# USB.net
KiCad netlist of a schematic drawn in Altium Designer
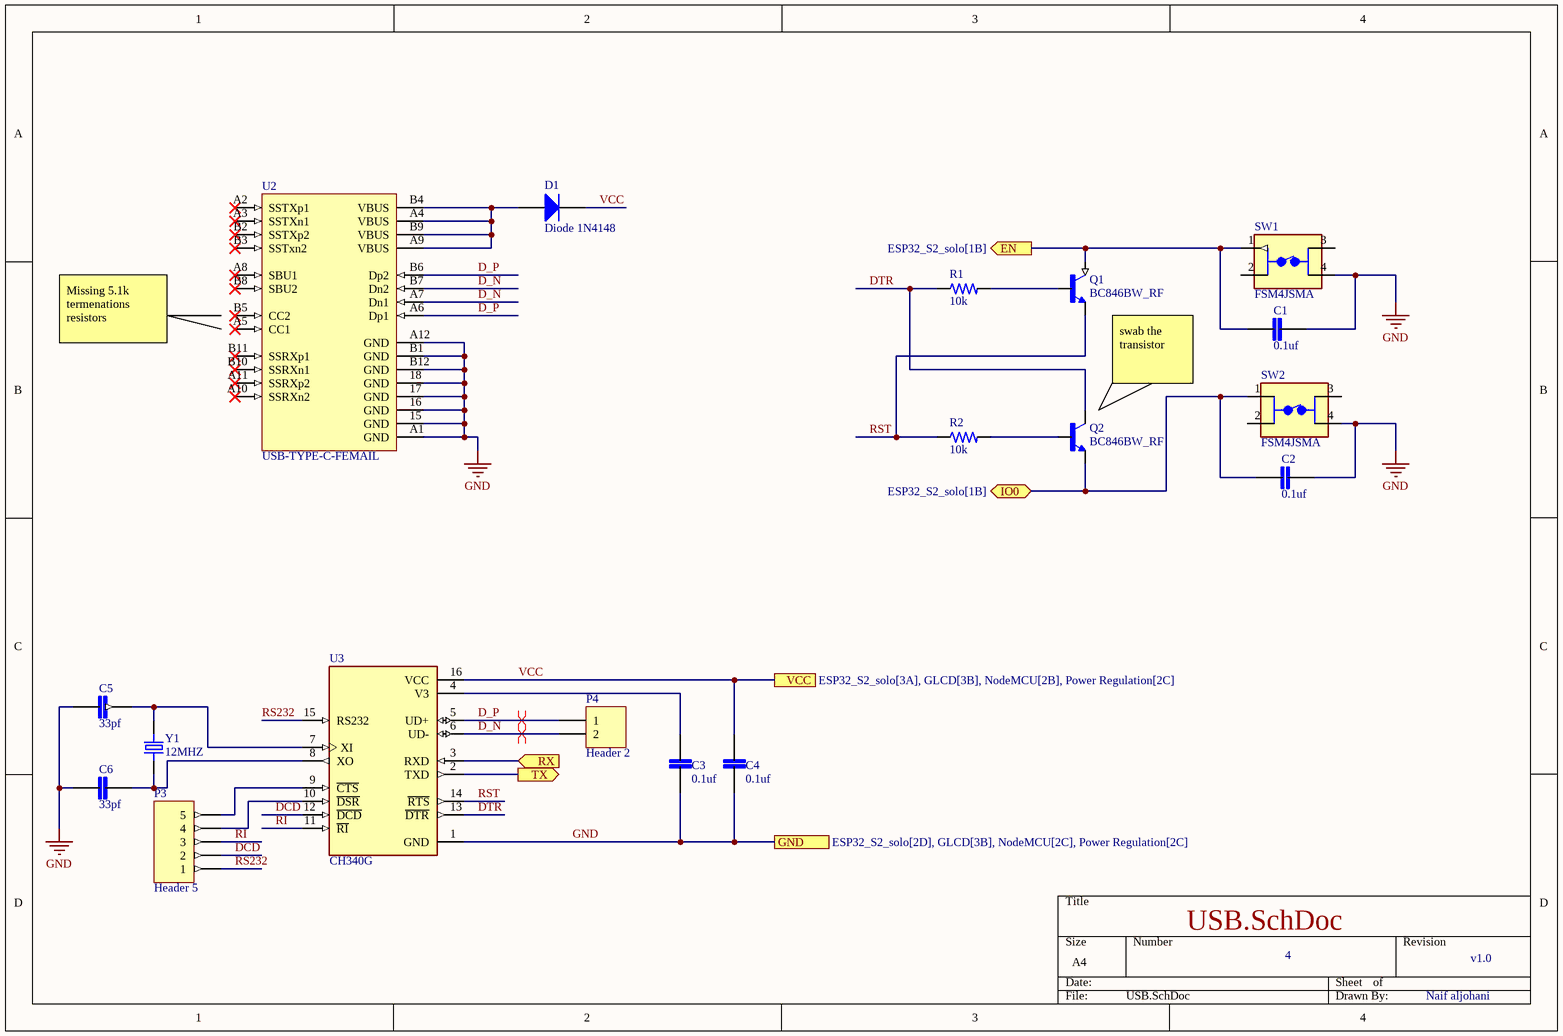
[diagram p0: USB.SchDoc]

(export (version "E")
  (design (tool "Eeschema 10.0.6"))
  (components
    (comp (ref "C1")
      (value "0.1uf")
      (footprint "CAPC2012X140N")
      (description "120PF 100V 10% 0805")
      (fields (field (name "MF") "{'manufacturer': u'AVX'}") (field (name "MP") "LD051A121KAB2A"))
      (libsource (lib "") (part "LD051A121KAB2A_2"))
    )
    (comp (ref "C2")
      (value "0.1uf")
      (footprint "CAPC2012X140N")
      (description "120PF 100V 10% 0805")
      (fields (field (name "MF") "{'manufacturer': u'AVX'}") (field (name "MP") "LD051A121KAB2A"))
      (libsource (lib "") (part "LD051A121KAB2A_2"))
    )
    (comp (ref "C3")
      (value "0.1uf")
      (footprint "CAPC2012X140N")
      (description "120PF 100V 10% 0805")
      (fields (field (name "MF") "{'manufacturer': u'AVX'}") (field (name "MP") "LD051A121KAB2A"))
      (libsource (lib "") (part "LD051A121KAB2A_1"))
    )
    (comp (ref "C4")
      (value "0.1uf")
      (footprint "CAPC2012X140N")
      (description "120PF 100V 10% 0805")
      (fields (field (name "MF") "{'manufacturer': u'AVX'}") (field (name "MP") "LD051A121KAB2A"))
      (libsource (lib "") (part "LD051A121KAB2A_1"))
    )
    (comp (ref "C5")
      (value "33pf")
      (footprint "CAPC2012X140N")
      (description "120PF 100V 10% 0805")
      (fields (field (name "MF") "{'manufacturer': u'AVX'}") (field (name "MP") "LD051A121KAB2A"))
      (libsource (lib "SnapEDA_Library") (part "LD051A121KAB2A"))
    )
    (comp (ref "C6")
      (value "33pf")
      (footprint "CAPC2012X140N")
      (description "120PF 100V 10% 0805")
      (fields (field (name "MF") "{'manufacturer': u'AVX'}") (field (name "MP") "LD051A121KAB2A"))
      (libsource (lib "SnapEDA_Library") (part "LD051A121KAB2A"))
    )
    (comp (ref "D1")
      (value "Diode 1N4148")
      (footprint "DO-35")
      (description "High Conductance Fast Diode")
      (fields (field (name "PUBLISHER") "Altium Limited"))
      (libsource (lib "Miscellaneous Devices") (part "Diode 1N4148"))
    )
    (comp (ref "P3")
      (value "Header 5")
      (footprint "HDR1X5")
      (description "Header, 5-Pin")
      (fields (field (name "PUBLISHER") "Altium Limited"))
      (libsource (lib "Miscellaneous Connectors") (part "Header 5"))
    )
    (comp (ref "P4")
      (value "Header 2")
      (footprint "HDR1X2")
      (description "Header, 2-Pin")
      (fields (field (name "PUBLISHER") "Altium Limited"))
      (libsource (lib "Miscellaneous Connectors") (part "Header 2"))
    )
    (comp (ref "Q1")
      (value "BC846BW_RF")
      (footprint "TRANS_BC846BW_RF")
      (fields (field (name "MF") "{'manufacturer': u'Taiwan Semiconductor'}"))
      (libsource (lib "SnapEDA_Library") (part "BC846BW_RF"))
    )
    (comp (ref "Q2")
      (value "BC846BW_RF")
      (footprint "TRANS_BC846BW_RF")
      (fields (field (name "MF") "{'manufacturer': u'Taiwan Semiconductor'}"))
      (libsource (lib "SnapEDA_Library") (part "BC846BW_RF"))
    )
    (comp (ref "R1")
      (value "10k")
      (footprint "RESC3115X65N")
      (description "RL73H 2B R43 1% 10 RL")
      (fields (field (name "MF") "{'manufacturer': u'TE Connectivity'}") (field (name "MP") "1-1879462-4"))
      (libsource (lib "SnapEDA_Library") (part "1-1879462-4"))
    )
    (comp (ref "R2")
      (value "10k")
      (footprint "RESC3115X65N")
      (description "RL73H 2B R43 1% 10 RL")
      (fields (field (name "MF") "{'manufacturer': u'TE Connectivity'}") (field (name "MP") "1-1879462-4"))
      (libsource (lib "SnapEDA_Library") (part "1-1879462-4"))
    )
    (comp (ref "SW1")
      (value "FSM4JSMA")
      (footprint "TE_FSM4JSMA")
      (description "Switch Tactile OFF (ON) SPST Round Button Gull Wing 0.05A 24VDC 2.6N SMD T/R")
      (fields (field (name "MF") "{'manufacturer': u'TE Connectivity'}"))
      (libsource (lib "SnapEDA_Library") (part "FSM4JSMA"))
    )
    (comp (ref "SW2")
      (value "FSM4JSMA")
      (footprint "TE_FSM4JSMA")
      (description "Switch Tactile OFF (ON) SPST Round Button Gull Wing 0.05A 24VDC 2.6N SMD T/R")
      (fields (field (name "MF") "{'manufacturer': u'TE Connectivity'}"))
      (libsource (lib "SnapEDA_Library") (part "FSM4JSMA"))
    )
    (comp (ref "U2")
      (value "USB-TYPE-C-FEMAIL")
      (footprint "C5156605")
      (libsource (lib "Schlib2") (part "USB-TYPE-C-FEMAIL"))
    )
    (comp (ref "U3")
      (value "CH340G")
      (footprint "SOIC127P600X180-16N")
      (fields (field (name "MF") "{'manufacturer': u'WCH'}"))
      (libsource (lib "SnapEDA_Library") (part "CH340G"))
    )
    (comp (ref "Y1")
      (value "12MHZ")
      (footprint "XTAL_ECS-51-S-1")
      (fields (field (name "MF") "{'manufacturer': u'ECS'}") (field (name "MP") "ECS-51-S-1"))
      (libsource (lib "SnapEDA_Library") (part "ECS-51-S-1"))
    )
  )
  (nets
    (net (code "1") (name "/DCD") (class "Default")
      (node (ref "P3") (pin "2") (pinfunction "2_2") (pintype "output"))
      (node (ref "U3") (pin "12") (pinfunction "~{DCD}_12") (pintype "input"))
    )
    (net (code "2") (name "/DTR") (class "Default")
      (node (ref "Q2") (pin "3") (pinfunction "C_3") (pintype "input"))
      (node (ref "R1") (pin "1") (pinfunction "1_1") (pintype "passive"))
      (node (ref "U3") (pin "13") (pinfunction "~{DTR}_13") (pintype "output"))
    )
    (net (code "3") (name "/D_N") (class "Default")
      (node (ref "P4") (pin "2") (pinfunction "2_2") (pintype "passive"))
      (node (ref "U2") (pin "A7") (pinfunction "Dn1_A7") (pintype "input"))
      (node (ref "U2") (pin "B7") (pinfunction "Dn2_B7") (pintype "input"))
      (node (ref "U3") (pin "6") (pinfunction "UD-_6") (pintype "bidirectional"))
    )
    (net (code "4") (name "/D_P") (class "Default")
      (node (ref "P4") (pin "1") (pinfunction "1_1") (pintype "passive"))
      (node (ref "U2") (pin "A6") (pinfunction "Dp1_A6") (pintype "input"))
      (node (ref "U2") (pin "B6") (pinfunction "Dp2_B6") (pintype "input"))
      (node (ref "U3") (pin "5") (pinfunction "UD+_5") (pintype "bidirectional"))
    )
    (net (code "5") (name "/EN") (class "Default")
      (node (ref "C1") (pin "1") (pinfunction "1_1") (pintype "passive"))
      (node (ref "Q1") (pin "3") (pinfunction "C_3") (pintype "input"))
      (node (ref "SW1") (pin "1") (pinfunction "1_1") (pintype "output"))
    )
    (net (code "6") (name "/IO0") (class "Default")
      (node (ref "C2") (pin "1") (pinfunction "1_1") (pintype "passive"))
      (node (ref "Q2") (pin "2") (pinfunction "E_2") (pintype "passive"))
      (node (ref "SW2") (pin "1") (pinfunction "1_1") (pintype "output"))
    )
    (net (code "7") (name "/RI") (class "Default")
      (node (ref "P3") (pin "3") (pinfunction "3_3") (pintype "output"))
      (node (ref "U3") (pin "11") (pinfunction "~{RI}_11") (pintype "input"))
    )
    (net (code "8") (name "/RS232") (class "Default")
      (node (ref "P3") (pin "1") (pinfunction "1_1") (pintype "output"))
      (node (ref "U3") (pin "15") (pinfunction "RS232_15") (pintype "input"))
    )
    (net (code "9") (name "/RST") (class "Default")
      (node (ref "Q1") (pin "2") (pinfunction "E_2") (pintype "passive"))
      (node (ref "R2") (pin "1") (pinfunction "1_1") (pintype "passive"))
      (node (ref "U3") (pin "14") (pinfunction "~{RTS}_14") (pintype "output"))
    )
    (net (code "10") (name "/RX") (class "Default")
      (node (ref "U3") (pin "3") (pinfunction "RXD_3") (pintype "input"))
    )
    (net (code "11") (name "/TX") (class "Default")
      (node (ref "U3") (pin "2") (pinfunction "TXD_2") (pintype "output"))
    )
    (net (code "12") (name "/VCC") (class "Default")
      (node (ref "C4") (pin "2") (pinfunction "2_2") (pintype "passive"))
      (node (ref "D1") (pin "2") (pinfunction "K_2") (pintype "passive"))
      (node (ref "U3") (pin "16") (pinfunction "VCC_16") (pintype "power_in"))
    )
    (net (code "13") (name "GND") (class "Default")
      (node (ref "C1") (pin "2") (pinfunction "2_2") (pintype "passive"))
      (node (ref "C2") (pin "2") (pinfunction "2_2") (pintype "passive"))
      (node (ref "C3") (pin "1") (pinfunction "1_1") (pintype "passive"))
      (node (ref "C4") (pin "1") (pinfunction "1_1") (pintype "passive"))
      (node (ref "C5") (pin "2") (pinfunction "2_2") (pintype "passive"))
      (node (ref "C6") (pin "2") (pinfunction "2_2") (pintype "passive"))
      (node (ref "SW1") (pin "4") (pinfunction "4_4") (pintype "passive"))
      (node (ref "SW2") (pin "4") (pinfunction "4_4") (pintype "passive"))
      (node (ref "U2") (pin "15") (pinfunction "GND_15") (pintype "power_in"))
      (node (ref "U2") (pin "16") (pinfunction "GND_16") (pintype "power_in"))
      (node (ref "U2") (pin "17") (pinfunction "GND_17") (pintype "power_in"))
      (node (ref "U2") (pin "18") (pinfunction "GND_18") (pintype "power_in"))
      (node (ref "U2") (pin "A1") (pinfunction "GND_A1") (pintype "power_in"))
      (node (ref "U2") (pin "A12") (pinfunction "GND_A12") (pintype "power_in"))
      (node (ref "U2") (pin "B1") (pinfunction "GND_B1") (pintype "power_in"))
      (node (ref "U2") (pin "B12") (pinfunction "GND_B12") (pintype "power_in"))
      (node (ref "U3") (pin "1") (pinfunction "GND_1") (pintype "power_in"))
    )
    (net (code "14") (name "Net-(D1-A)") (class "Default")
      (node (ref "D1") (pin "1") (pinfunction "A_1") (pintype "passive"))
      (node (ref "U2") (pin "A4") (pinfunction "VBUS_A4") (pintype "power_in"))
      (node (ref "U2") (pin "A9") (pinfunction "VBUS_A9") (pintype "power_in"))
      (node (ref "U2") (pin "B4") (pinfunction "VBUS_B4") (pintype "power_in"))
      (node (ref "U2") (pin "B9") (pinfunction "VBUS_B9") (pintype "power_in"))
    )
    (net (code "15") (name "Net-(Q1-B)") (class "Default")
      (node (ref "Q1") (pin "1") (pinfunction "B_1") (pintype "passive"))
      (node (ref "R1") (pin "2") (pinfunction "2_2") (pintype "passive"))
    )
    (net (code "16") (name "Net-(Q2-B)") (class "Default")
      (node (ref "Q2") (pin "1") (pinfunction "B_1") (pintype "passive"))
      (node (ref "R2") (pin "2") (pinfunction "2_2") (pintype "passive"))
    )
    (net (code "17") (name "Net-(U3-V3)") (class "Default")
      (node (ref "C3") (pin "2") (pinfunction "2_2") (pintype "passive"))
      (node (ref "U3") (pin "4") (pinfunction "V3_4") (pintype "power_in"))
    )
    (net (code "18") (name "Net-(U3-XI)") (class "Default")
      (node (ref "C5") (pin "1") (pinfunction "1_1") (pintype "passive"))
      (node (ref "U3") (pin "7") (pinfunction "XI_7") (pintype "input"))
      (node (ref "Y1") (pin "2") (pinfunction "2_2") (pintype "passive"))
    )
    (net (code "19") (name "Net-(U3-XO)") (class "Default")
      (node (ref "C6") (pin "1") (pinfunction "1_1") (pintype "passive"))
      (node (ref "U3") (pin "8") (pinfunction "XO_8") (pintype "output"))
      (node (ref "Y1") (pin "1") (pinfunction "1_1") (pintype "passive"))
    )
    (net (code "20") (name "Net-(U3-~{CTS})") (class "Default")
      (node (ref "P3") (pin "5") (pinfunction "5_5") (pintype "output"))
      (node (ref "U3") (pin "9") (pinfunction "~{CTS}_9") (pintype "input"))
    )
    (net (code "21") (name "Net-(U3-~{DSR})") (class "Default")
      (node (ref "P3") (pin "4") (pinfunction "4_4") (pintype "output"))
      (node (ref "U3") (pin "10") (pinfunction "~{DSR}_10") (pintype "input"))
    )
    (net (code "22") (name "unconnected-(SW1-Pad2)") (class "Default")
      (node (ref "SW1") (pin "2") (pinfunction "2_2") (pintype "passive"))
    )
    (net (code "23") (name "unconnected-(SW1-Pad3)") (class "Default")
      (node (ref "SW1") (pin "3") (pinfunction "3_3") (pintype "passive"))
    )
    (net (code "24") (name "unconnected-(SW2-Pad2)") (class "Default")
      (node (ref "SW2") (pin "2") (pinfunction "2_2") (pintype "passive"))
    )
    (net (code "25") (name "unconnected-(SW2-Pad3)") (class "Default")
      (node (ref "SW2") (pin "3") (pinfunction "3_3") (pintype "passive"))
    )
    (net (code "26") (name "unconnected-(U2-CC1-PadA5)") (class "Default")
      (node (ref "U2") (pin "A5") (pinfunction "CC1_A5") (pintype "input+no_connect"))
    )
    (net (code "27") (name "unconnected-(U2-CC2-PadB5)") (class "Default")
      (node (ref "U2") (pin "B5") (pinfunction "CC2_B5") (pintype "input+no_connect"))
    )
    (net (code "28") (name "unconnected-(U2-SBU1-PadA8)") (class "Default")
      (node (ref "U2") (pin "A8") (pinfunction "SBU1_A8") (pintype "input+no_connect"))
    )
    (net (code "29") (name "unconnected-(U2-SBU2-PadB8)") (class "Default")
      (node (ref "U2") (pin "B8") (pinfunction "SBU2_B8") (pintype "input+no_connect"))
    )
    (net (code "30") (name "unconnected-(U2-SSRXn1-PadB10)") (class "Default")
      (node (ref "U2") (pin "B10") (pinfunction "SSRXn1_B10") (pintype "input+no_connect"))
    )
    (net (code "31") (name "unconnected-(U2-SSRXn2-PadA10)") (class "Default")
      (node (ref "U2") (pin "A10") (pinfunction "SSRXn2_A10") (pintype "input+no_connect"))
    )
    (net (code "32") (name "unconnected-(U2-SSRXp1-PadB11)") (class "Default")
      (node (ref "U2") (pin "B11") (pinfunction "SSRXp1_B11") (pintype "input+no_connect"))
    )
    (net (code "33") (name "unconnected-(U2-SSRXp2-PadA11)") (class "Default")
      (node (ref "U2") (pin "A11") (pinfunction "SSRXp2_A11") (pintype "input+no_connect"))
    )
    (net (code "34") (name "unconnected-(U2-SSTXn1-PadA3)") (class "Default")
      (node (ref "U2") (pin "A3") (pinfunction "SSTXn1_A3") (pintype "input+no_connect"))
    )
    (net (code "35") (name "unconnected-(U2-SSTXp1-PadA2)") (class "Default")
      (node (ref "U2") (pin "A2") (pinfunction "SSTXp1_A2") (pintype "input+no_connect"))
    )
    (net (code "36") (name "unconnected-(U2-SSTXp2-PadB2)") (class "Default")
      (node (ref "U2") (pin "B2") (pinfunction "SSTXp2_B2") (pintype "input+no_connect"))
    )
    (net (code "37") (name "unconnected-(U2-SSTxn2-PadB3)") (class "Default")
      (node (ref "U2") (pin "B3") (pinfunction "SSTxn2_B3") (pintype "input+no_connect"))
    )
  )
)
